# Radar_FMCW.net
KiCad netlist of a schematic drawn in Altium Designer
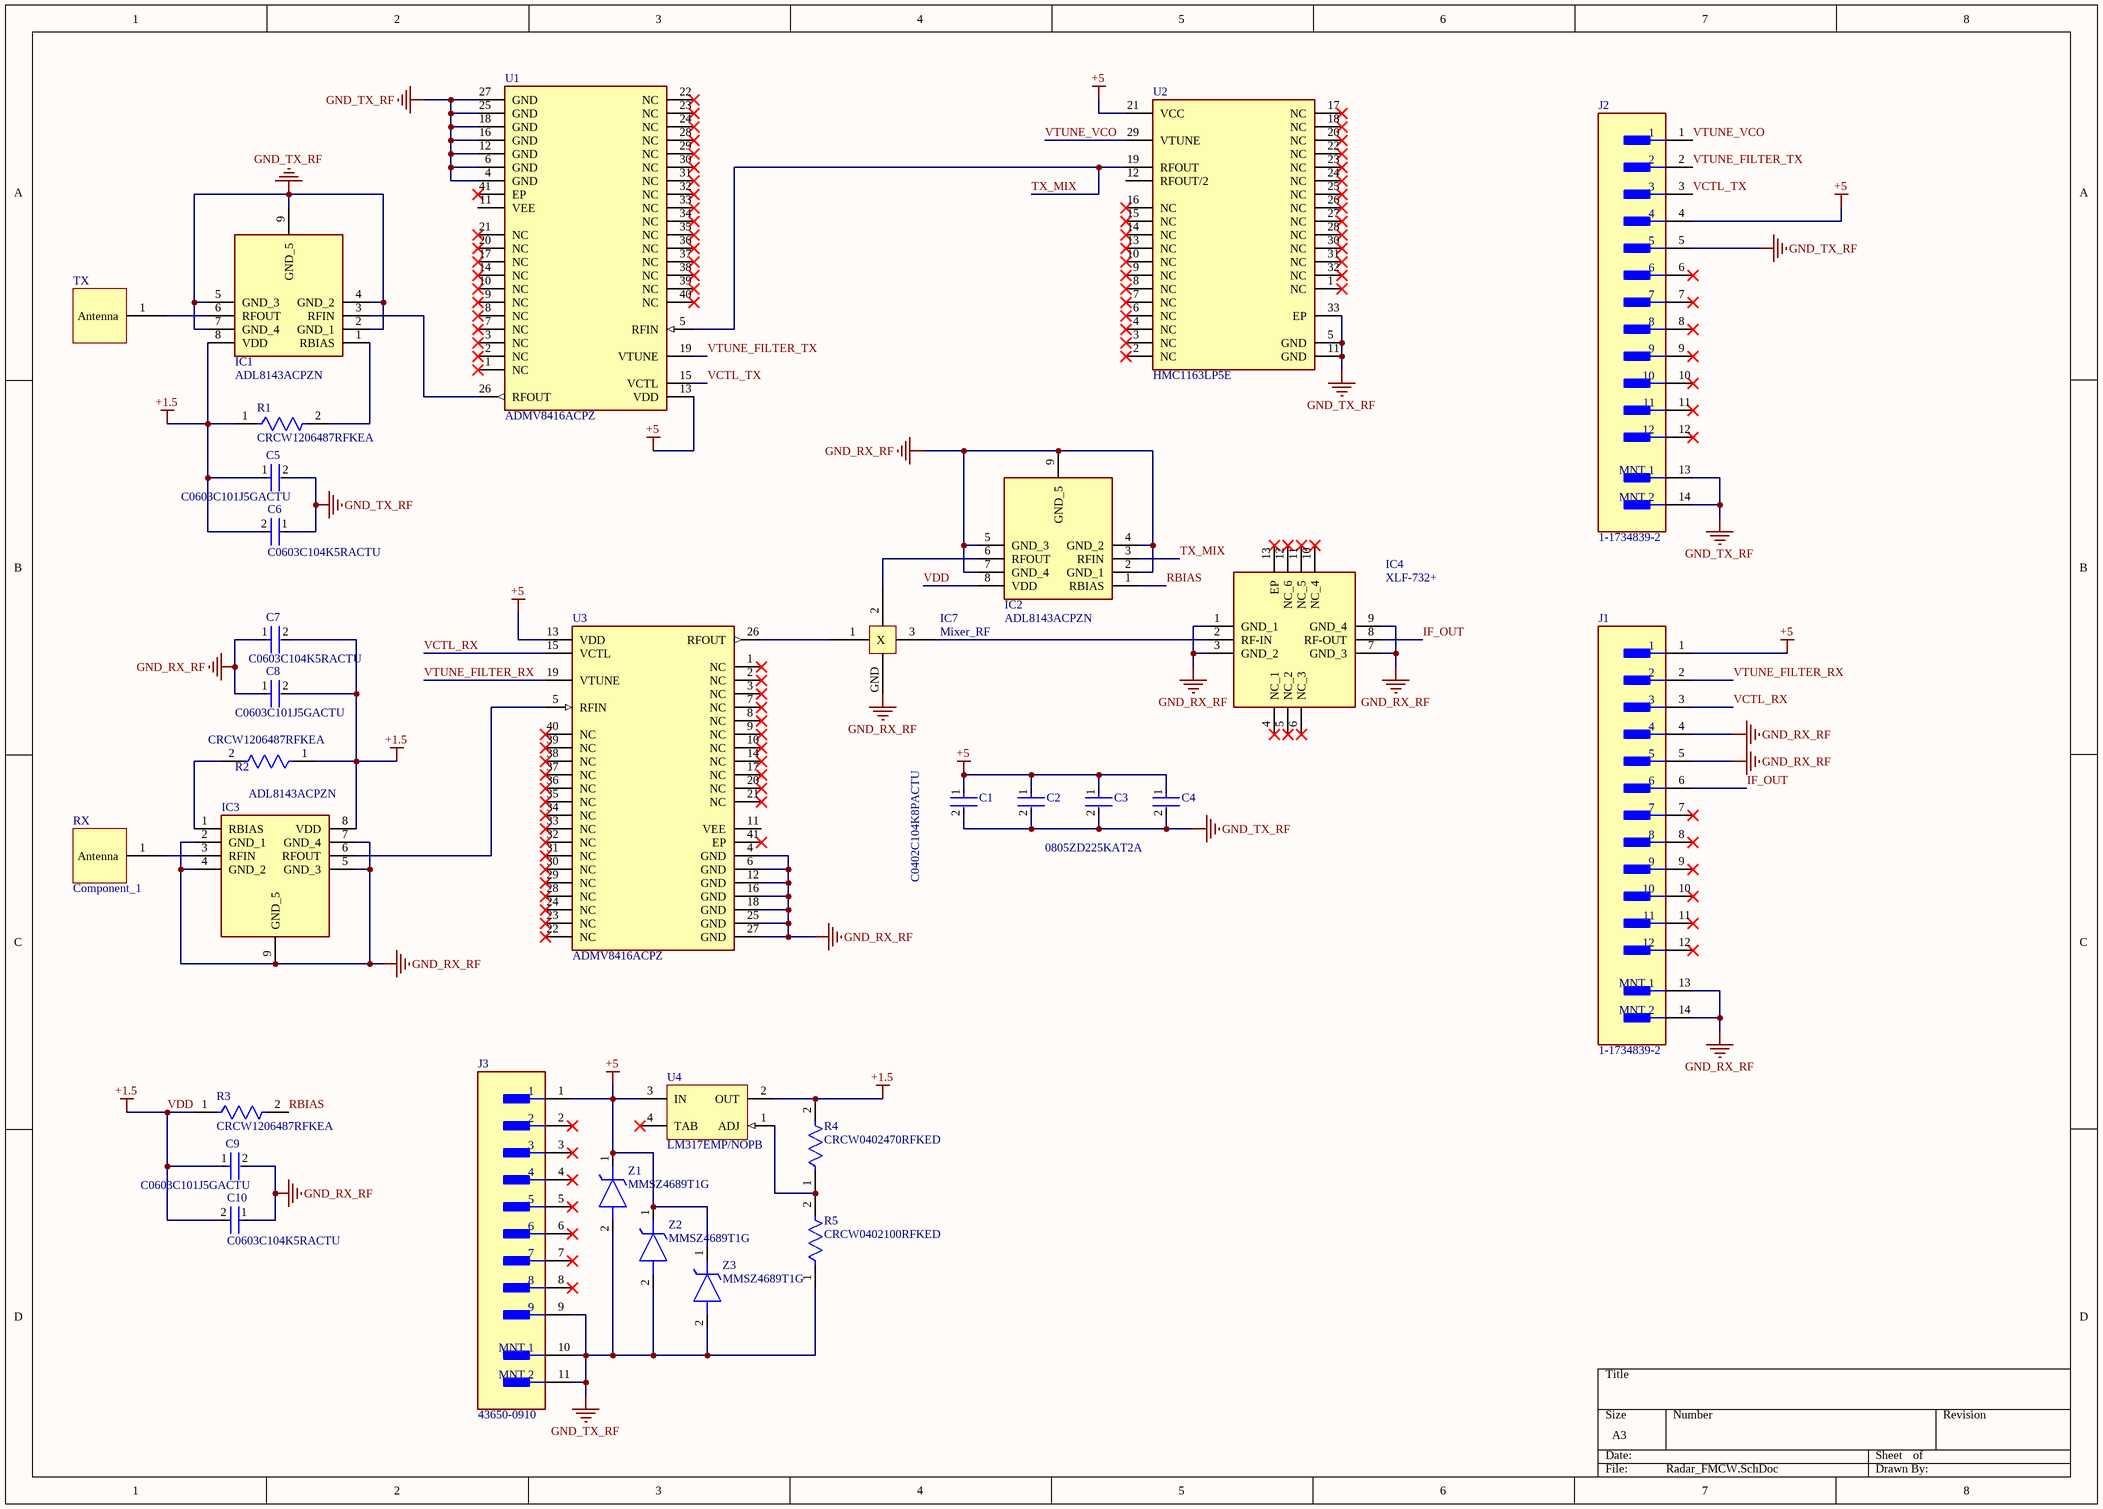
[diagram p0: Radar_FMCW.SchDoc]

(export (version "E")
  (design (tool "Eeschema 10.0.6"))
  (components
    (comp (ref "C1")
      (value "C0402C104K8PACTU")
      (footprint "FP-C0402-BB-MFG")
      (description "CAP CER 0.1UF 10V X5R 0402")
      (fields (field (name "MANUFACTURER") "Kemet") (field (name "TOLERANCE") "0.1"))
      (libsource (lib "Altium Content Vault") (part "b4654b650e69147ec39a6b967a45e02"))
    )
    (comp (ref "C2")
      (value "~")
      (footprint "FP-0805-L_2_01_0_2-W_1_25-IPC_B")
      (description "General Purpose Ceramic Capacitor, 0805, 2.2uF, 10%, X5R, 15%, 10V")
      (fields (field (name "VOLTAGE") "10V") (field (name "TOLERANCE") "10%"))
      (libsource (lib "Altium Content Vault") (part "b4654b650e69147ec39a6b967a45e02"))
    )
    (comp (ref "C3")
      (value "~")
      (footprint "FP-0805-L_2_01_0_2-W_1_25-IPC_B")
      (description "General Purpose Ceramic Capacitor, 0805, 2.2uF, 10%, X5R, 15%, 10V")
      (fields (field (name "VOLTAGE") "10V") (field (name "TOLERANCE") "10%"))
      (libsource (lib "Altium Content Vault") (part "b4654b650e69147ec39a6b967a45e02"))
    )
    (comp (ref "C4")
      (value "0805ZD225KAT2A")
      (footprint "FP-0805-L_2_01_0_2-W_1_25-IPC_B")
      (description "General Purpose Ceramic Capacitor, 0805, 2.2uF, 10%, X5R, 15%, 10V")
      (fields (field (name "VOLTAGE") "10V") (field (name "TOLERANCE") "10%"))
      (libsource (lib "Altium Content Vault") (part "b4654b650e69147ec39a6b967a45e02"))
    )
    (comp (ref "C5")
      (value "C0603C101J5GACTU")
      (footprint "FP-C0603C-CF-MFG")
      (description "CAP CER 100PF 50V C0G/NP0 0603")
      (fields (field (name "TOLERANCE") "0.05") (field (name "MANUFACTURER") "KEMET"))
      (libsource (lib "Altium Content Vault") (part "b4654b650e69147ec39a6b967a45e02"))
    )
    (comp (ref "C6")
      (value "C0603C104K5RACTU")
      (footprint "FP-C0603C-CF-MFG")
      (description "CAP CER 0.1UF 50V X7R 0603")
      (fields (field (name "TOLERANCE") "0.1") (field (name "MANUFACTURER") "KEMET"))
      (libsource (lib "Altium Content Vault") (part "b4654b650e69147ec39a6b967a45e02"))
    )
    (comp (ref "C7")
      (value "C0603C104K5RACTU")
      (footprint "FP-C0603C-CF-MFG")
      (description "CAP CER 0.1UF 50V X7R 0603")
      (fields (field (name "TOLERANCE") "0.1") (field (name "MANUFACTURER") "KEMET"))
      (libsource (lib "Altium Content Vault") (part "b4654b650e69147ec39a6b967a45e02"))
    )
    (comp (ref "C8")
      (value "C0603C101J5GACTU")
      (footprint "FP-C0603C-CF-MFG")
      (description "CAP CER 100PF 50V C0G/NP0 0603")
      (fields (field (name "TOLERANCE") "0.05") (field (name "MANUFACTURER") "KEMET"))
      (libsource (lib "Altium Content Vault") (part "b4654b650e69147ec39a6b967a45e02"))
    )
    (comp (ref "C9")
      (value "C0603C101J5GACTU")
      (footprint "FP-C0603C-CF-MFG")
      (description "CAP CER 100PF 50V C0G/NP0 0603")
      (fields (field (name "TOLERANCE") "0.05") (field (name "MANUFACTURER") "KEMET"))
      (libsource (lib "Altium Content Vault") (part "b4654b650e69147ec39a6b967a45e02"))
    )
    (comp (ref "C10")
      (value "C0603C104K5RACTU")
      (footprint "FP-C0603C-CF-MFG")
      (description "CAP CER 0.1UF 50V X7R 0603")
      (fields (field (name "TOLERANCE") "0.1") (field (name "MANUFACTURER") "KEMET"))
      (libsource (lib "Altium Content Vault") (part "b4654b650e69147ec39a6b967a45e02"))
    )
    (comp (ref "IC1")
      (value "ADL8143ACPZN")
      (footprint "SON50P200X200X90-9N-D")
      (description "Integrated Circuit")
      (libsource (lib "*") (part "ADL8143ACPZN"))
    )
    (comp (ref "IC2")
      (value "ADL8143ACPZN")
      (footprint "SON50P200X200X90-9N-D")
      (description "Integrated Circuit")
      (libsource (lib "*") (part "ADL8143ACPZN"))
    )
    (comp (ref "IC3")
      (value "ADL8143ACPZN")
      (footprint "SON50P200X200X90-9N-D")
      (description "Integrated Circuit")
      (libsource (lib "") (part "ADL8143ACPZN_1"))
    )
    (comp (ref "IC4")
      (value "XLF-732+")
      (footprint "QFN51P300X300X89-13N")
      (description "Integrated Circuit")
      (fields (field (name "MOUSER PART NUMBER") "139-XLF-732"))
      (libsource (lib "*") (part "XLF-732+"))
    )
    (comp (ref "IC7")
      (value "Mixer_RF")
      (footprint "Mixer_RF")
      (libsource (lib "Radar_FMCW") (part "Mixer_RF"))
    )
    (comp (ref "J1")
      (value "1-1734839-2")
      (footprint "FP-1-1734839-2-MFG")
      (description "CONN FPC TOP 12POS 0.50MM R/A")
      (libsource (lib "Altium Content Vault") (part "561d9104b8f291ee0c4fa0e805f8bc4"))
    )
    (comp (ref "J2")
      (value "1-1734839-2")
      (footprint "FP-1-1734839-2-MFG")
      (description "CONN FPC TOP 12POS 0.50MM R/A")
      (libsource (lib "Altium Content Vault") (part "561d9104b8f291ee0c4fa0e805f8bc4"))
    )
    (comp (ref "J3")
      (value "43650-0910")
      (footprint "FP-43650-0910-MFG")
      (description "43650-0910 Conn Power HDR 9 POS 3mm Solder RA SMD 9 Terminal 1 Port Micro-Fit 3.0™ Embossed T/R")
      (libsource (lib "Altium Content Vault") (part "1768e92021096bf704ffca471e34b85"))
    )
    (comp (ref "R1")
      (value "CRCW1206487RFKEA")
      (footprint "FP-CRCW1206-e3-MFG")
      (description "RES Thick Film, 487Ω, 1%, 0.25W, 100ppm/°C, 1206")
      (fields (field (name "TOLERANCE") "1%"))
      (libsource (lib "Altium Content Vault") (part "1029c3af85768c4190bb7ad29bc67b5"))
    )
    (comp (ref "R2")
      (value "CRCW1206487RFKEA")
      (footprint "FP-CRCW1206-e3-MFG")
      (description "RES Thick Film, 487Ω, 1%, 0.25W, 100ppm/°C, 1206")
      (fields (field (name "TOLERANCE") "1%"))
      (libsource (lib "Altium Content Vault") (part "1029c3af85768c4190bb7ad29bc67b5"))
    )
    (comp (ref "R3")
      (value "CRCW1206487RFKEA")
      (footprint "FP-CRCW1206-e3-MFG")
      (description "RES Thick Film, 487Ω, 1%, 0.25W, 100ppm/°C, 1206")
      (fields (field (name "TOLERANCE") "1%"))
      (libsource (lib "Altium Content Vault") (part "1029c3af85768c4190bb7ad29bc67b5"))
    )
    (comp (ref "R4")
      (value "CRCW0402470RFKED")
      (footprint "FP-CRCW0402-e3-MFG")
      (description "RES Thick Film, 470Ω, 1%, 0.063W, 100ppm/°C, 0402")
      (fields (field (name "TOLERANCE") "1%"))
      (libsource (lib "Altium Content Vault") (part "1029c3af85768c4190bb7ad29bc67b5"))
    )
    (comp (ref "R5")
      (value "CRCW0402100RFKED")
      (footprint "FP-CRCW0402-e3-IPC_C")
      (description "RES Thick Film, 100Ω, 1%, 0.063W, 100ppm/°C, 0402")
      (fields (field (name "TOLERANCE") "1%"))
      (libsource (lib "Altium Content Vault") (part "1029c3af85768c4190bb7ad29bc67b5"))
    )
    (comp (ref "RX")
      (value "Component_1")
      (footprint "Antenna_10GHz")
      (libsource (lib "Radar_FMCW") (part "Component_1"))
    )
    (comp (ref "TX")
      (value "~")
      (footprint "Antenna_10GHz")
      (libsource (lib "Radar_FMCW") (part "Component_1"))
    )
    (comp (ref "U1")
      (value "ADMV8416ACPZ")
      (footprint "FP-CP-40-27-IPC_C")
      (description "8 TO 16 GHZ TUNABLE BPF")
      (libsource (lib "Altium Content Vault") (part "eb4e6505d990d040ba8ad15b459702c"))
    )
    (comp (ref "U2")
      (value "HMC1163LP5E")
      (footprint "FP-HCP-32-1-IPC_B")
      (description "IC VCO VSAT 9.65-10.41GHZ 32CSP")
      (libsource (lib "Altium Content Vault") (part "3a6c81b600e4c804ad769945137bfc4"))
    )
    (comp (ref "U3")
      (value "ADMV8416ACPZ")
      (footprint "FP-CP-40-27-IPC_C")
      (description "8 TO 16 GHZ TUNABLE BPF")
      (libsource (lib "") (part "eb4e6505d990d040ba8ad15b459702c_1"))
    )
    (comp (ref "U4")
      (value "LM317EMP/NOPB")
      (footprint "DCY0004A_L")
      (description "3-Terminal Adjustable Regulator, 4-pin SOT-223, Pb-Free")
      (fields (field (name "MANUFACTURER") "Texas Instruments"))
      (libsource (lib "Altium Content Vault") (part "PM-REG-LM317ADJ-SOT4"))
    )
    (comp (ref "Z1")
      (value "MMSZ4689T1G")
      (footprint "Radar_FMCW:SOD3716X135N")
      (description "Zener Diode")
      (fields (field (name "MOUSER PART NUMBER") "863-MMSZ4689T1G"))
      (libsource (lib "*") (part "MMSZ4689T1G"))
    )
    (comp (ref "Z2")
      (value "MMSZ4689T1G")
      (footprint "Radar_FMCW:SOD3716X135N")
      (description "Zener Diode")
      (fields (field (name "MOUSER PART NUMBER") "863-MMSZ4689T1G"))
      (libsource (lib "*") (part "MMSZ4689T1G"))
    )
    (comp (ref "Z3")
      (value "MMSZ4689T1G")
      (footprint "Radar_FMCW:SOD3716X135N")
      (description "Zener Diode")
      (fields (field (name "MOUSER PART NUMBER") "863-MMSZ4689T1G"))
      (libsource (lib "*") (part "MMSZ4689T1G"))
    )
  )
  (nets
    (net (code "1") (name "+1.5") (class "Default")
      (node (ref "C10") (pin "2") (pinfunction "2_2") (pintype "passive"))
      (node (ref "C5") (pin "1") (pinfunction "1_1") (pintype "passive"))
      (node (ref "C6") (pin "2") (pinfunction "2_2") (pintype "passive"))
      (node (ref "C7") (pin "2") (pinfunction "2_2") (pintype "passive"))
      (node (ref "C8") (pin "2") (pinfunction "2_2") (pintype "passive"))
      (node (ref "C9") (pin "1") (pinfunction "1_1") (pintype "passive"))
      (node (ref "IC1") (pin "8") (pinfunction "VDD_8") (pintype "passive"))
      (node (ref "IC2") (pin "8") (pinfunction "VDD_8") (pintype "passive"))
      (node (ref "IC3") (pin "8") (pinfunction "VDD_8") (pintype "passive"))
      (node (ref "R1") (pin "1") (pinfunction "1_1") (pintype "passive"))
      (node (ref "R2") (pin "1") (pinfunction "1_1") (pintype "passive"))
      (node (ref "R3") (pin "1") (pinfunction "1_1") (pintype "passive"))
      (node (ref "R4") (pin "2") (pinfunction "2_2") (pintype "passive"))
      (node (ref "U4") (pin "2") (pinfunction "OUT_2") (pintype "power_in"))
    )
    (net (code "2") (name "+5") (class "Default")
      (node (ref "C1") (pin "1") (pinfunction "1_1") (pintype "passive"))
      (node (ref "C2") (pin "1") (pinfunction "1_1") (pintype "passive"))
      (node (ref "C3") (pin "1") (pinfunction "1_1") (pintype "passive"))
      (node (ref "C4") (pin "1") (pinfunction "1_1") (pintype "passive"))
      (node (ref "J1") (pin "1") (pinfunction "1_1") (pintype "passive"))
      (node (ref "J2") (pin "4") (pinfunction "4_4") (pintype "passive"))
      (node (ref "J3") (pin "1") (pinfunction "1_1") (pintype "passive"))
      (node (ref "U1") (pin "13") (pinfunction "VDD_13") (pintype "power_in"))
      (node (ref "U2") (pin "21") (pinfunction "VCC_21") (pintype "power_in"))
      (node (ref "U3") (pin "13") (pinfunction "VDD_13") (pintype "power_in"))
      (node (ref "U4") (pin "3") (pinfunction "IN_3") (pintype "power_in"))
      (node (ref "Z1") (pin "1") (pinfunction "K_1") (pintype "passive"))
      (node (ref "Z2") (pin "1") (pinfunction "K_1") (pintype "passive"))
      (node (ref "Z3") (pin "1") (pinfunction "K_1") (pintype "passive"))
    )
    (net (code "3") (name "/IF_OUT") (class "Default")
      (node (ref "IC4") (pin "8") (pinfunction "RF-OUT_8") (pintype "passive"))
      (node (ref "J1") (pin "6") (pinfunction "6_6") (pintype "passive"))
    )
    (net (code "4") (name "/RBIAS") (class "Default")
      (node (ref "IC2") (pin "1") (pinfunction "RBIAS_1") (pintype "passive"))
      (node (ref "R3") (pin "2") (pinfunction "2_2") (pintype "passive"))
    )
    (net (code "5") (name "/TX_MIX") (class "Default")
      (node (ref "IC2") (pin "3") (pinfunction "RFIN_3") (pintype "passive"))
      (node (ref "U1") (pin "5") (pinfunction "RFIN_5") (pintype "input"))
      (node (ref "U2") (pin "19") (pinfunction "RFOUT_19") (pintype "passive"))
    )
    (net (code "6") (name "/VCTL_RX") (class "Default")
      (node (ref "J1") (pin "3") (pinfunction "3_3") (pintype "passive"))
      (node (ref "U3") (pin "15") (pinfunction "VCTL_15") (pintype "power_in"))
    )
    (net (code "7") (name "/VCTL_TX") (class "Default")
      (node (ref "J2") (pin "3") (pinfunction "3_3") (pintype "passive"))
      (node (ref "U1") (pin "15") (pinfunction "VCTL_15") (pintype "power_in"))
    )
    (net (code "8") (name "/VTUNE_FILTER_RX") (class "Default")
      (node (ref "J1") (pin "2") (pinfunction "2_2") (pintype "passive"))
      (node (ref "U3") (pin "19") (pinfunction "VTUNE_19") (pintype "power_in"))
    )
    (net (code "9") (name "/VTUNE_FILTER_TX") (class "Default")
      (node (ref "J2") (pin "2") (pinfunction "2_2") (pintype "passive"))
      (node (ref "U1") (pin "19") (pinfunction "VTUNE_19") (pintype "power_in"))
    )
    (net (code "10") (name "/VTUNE_VCO") (class "Default")
      (node (ref "J2") (pin "1") (pinfunction "1_1") (pintype "passive"))
      (node (ref "U2") (pin "29") (pinfunction "VTUNE_29") (pintype "power_in"))
    )
    (net (code "11") (name "GND_RX_RF") (class "Default")
      (node (ref "C10") (pin "1") (pinfunction "1_1") (pintype "passive"))
      (node (ref "C7") (pin "1") (pinfunction "1_1") (pintype "passive"))
      (node (ref "C8") (pin "1") (pinfunction "1_1") (pintype "passive"))
      (node (ref "C9") (pin "2") (pinfunction "2_2") (pintype "passive"))
      (node (ref "IC2") (pin "2") (pinfunction "GND_1_2") (pintype "passive"))
      (node (ref "IC2") (pin "4") (pinfunction "GND_2_4") (pintype "passive"))
      (node (ref "IC2") (pin "5") (pinfunction "GND_3_5") (pintype "passive"))
      (node (ref "IC2") (pin "7") (pinfunction "GND_4_7") (pintype "passive"))
      (node (ref "IC2") (pin "9") (pinfunction "GND_5_9") (pintype "passive"))
      (node (ref "IC3") (pin "2") (pinfunction "GND_1_2") (pintype "passive"))
      (node (ref "IC3") (pin "4") (pinfunction "GND_2_4") (pintype "passive"))
      (node (ref "IC3") (pin "5") (pinfunction "GND_3_5") (pintype "passive"))
      (node (ref "IC3") (pin "7") (pinfunction "GND_4_7") (pintype "passive"))
      (node (ref "IC3") (pin "9") (pinfunction "GND_5_9") (pintype "passive"))
      (node (ref "IC4") (pin "1") (pinfunction "GND_1_1") (pintype "passive"))
      (node (ref "IC4") (pin "3") (pinfunction "GND_2_3") (pintype "passive"))
      (node (ref "IC4") (pin "7") (pinfunction "GND_3_7") (pintype "passive"))
      (node (ref "IC4") (pin "9") (pinfunction "GND_4_9") (pintype "passive"))
      (node (ref "IC7") (pin "GND") (pintype "passive"))
      (node (ref "J1") (pin "13") (pinfunction "MNT_1_13") (pintype "passive"))
      (node (ref "J1") (pin "14") (pinfunction "MNT_2_14") (pintype "passive"))
      (node (ref "J1") (pin "4") (pinfunction "4_4") (pintype "passive"))
      (node (ref "J1") (pin "5") (pinfunction "5_5") (pintype "passive"))
      (node (ref "U3") (pin "12") (pinfunction "GND_12") (pintype "power_in"))
      (node (ref "U3") (pin "16") (pinfunction "GND_16") (pintype "power_in"))
      (node (ref "U3") (pin "18") (pinfunction "GND_18") (pintype "power_in"))
      (node (ref "U3") (pin "25") (pinfunction "GND_25") (pintype "power_in"))
      (node (ref "U3") (pin "27") (pinfunction "GND_27") (pintype "power_in"))
      (node (ref "U3") (pin "4") (pinfunction "GND_4") (pintype "power_in"))
      (node (ref "U3") (pin "6") (pinfunction "GND_6") (pintype "power_in"))
    )
    (net (code "12") (name "GND_TX_RF") (class "Default")
      (node (ref "C1") (pin "2") (pinfunction "2_2") (pintype "passive"))
      (node (ref "C2") (pin "2") (pinfunction "2_2") (pintype "passive"))
      (node (ref "C3") (pin "2") (pinfunction "2_2") (pintype "passive"))
      (node (ref "C4") (pin "2") (pinfunction "2_2") (pintype "passive"))
      (node (ref "C5") (pin "2") (pinfunction "2_2") (pintype "passive"))
      (node (ref "C6") (pin "1") (pinfunction "1_1") (pintype "passive"))
      (node (ref "IC1") (pin "2") (pinfunction "GND_1_2") (pintype "passive"))
      (node (ref "IC1") (pin "4") (pinfunction "GND_2_4") (pintype "passive"))
      (node (ref "IC1") (pin "5") (pinfunction "GND_3_5") (pintype "passive"))
      (node (ref "IC1") (pin "7") (pinfunction "GND_4_7") (pintype "passive"))
      (node (ref "IC1") (pin "9") (pinfunction "GND_5_9") (pintype "passive"))
      (node (ref "J2") (pin "13") (pinfunction "MNT_1_13") (pintype "passive"))
      (node (ref "J2") (pin "14") (pinfunction "MNT_2_14") (pintype "passive"))
      (node (ref "J2") (pin "5") (pinfunction "5_5") (pintype "passive"))
      (node (ref "J3") (pin "10") (pinfunction "MNT_1_10") (pintype "passive"))
      (node (ref "J3") (pin "11") (pinfunction "MNT_2_11") (pintype "passive"))
      (node (ref "J3") (pin "9") (pinfunction "9_9") (pintype "passive"))
      (node (ref "R5") (pin "1") (pinfunction "1_1") (pintype "passive"))
      (node (ref "U1") (pin "12") (pinfunction "GND_12") (pintype "power_in"))
      (node (ref "U1") (pin "16") (pinfunction "GND_16") (pintype "power_in"))
      (node (ref "U1") (pin "18") (pinfunction "GND_18") (pintype "power_in"))
      (node (ref "U1") (pin "25") (pinfunction "GND_25") (pintype "power_in"))
      (node (ref "U1") (pin "27") (pinfunction "GND_27") (pintype "power_in"))
      (node (ref "U1") (pin "4") (pinfunction "GND_4") (pintype "power_in"))
      (node (ref "U1") (pin "6") (pinfunction "GND_6") (pintype "power_in"))
      (node (ref "U2") (pin "11") (pinfunction "GND_11") (pintype "power_in"))
      (node (ref "U2") (pin "33") (pinfunction "EP_33") (pintype "passive"))
      (node (ref "U2") (pin "5") (pinfunction "GND_5") (pintype "power_in"))
      (node (ref "Z1") (pin "2") (pinfunction "A_2") (pintype "passive"))
      (node (ref "Z2") (pin "2") (pinfunction "A_2") (pintype "passive"))
      (node (ref "Z3") (pin "2") (pinfunction "A_2") (pintype "passive"))
    )
    (net (code "13") (name "Net-(IC1-RBIAS)") (class "Default")
      (node (ref "IC1") (pin "1") (pinfunction "RBIAS_1") (pintype "passive"))
      (node (ref "R1") (pin "2") (pinfunction "2_2") (pintype "passive"))
    )
    (net (code "14") (name "Net-(IC1-RFIN)") (class "Default")
      (node (ref "IC1") (pin "3") (pinfunction "RFIN_3") (pintype "passive"))
      (node (ref "U1") (pin "26") (pinfunction "RFOUT_26") (pintype "output"))
    )
    (net (code "15") (name "Net-(IC1-RFOUT)") (class "Default")
      (node (ref "IC1") (pin "6") (pinfunction "RFOUT_6") (pintype "passive"))
      (node (ref "TX") (pin "1") (pinfunction "Antenna_1") (pintype "passive"))
    )
    (net (code "16") (name "Net-(IC2-RFOUT)") (class "Default")
      (node (ref "IC2") (pin "6") (pinfunction "RFOUT_6") (pintype "passive"))
      (node (ref "IC7") (pin "2") (pintype "passive"))
    )
    (net (code "17") (name "Net-(IC3-RBIAS)") (class "Default")
      (node (ref "IC3") (pin "1") (pinfunction "RBIAS_1") (pintype "passive"))
      (node (ref "R2") (pin "2") (pinfunction "2_2") (pintype "passive"))
    )
    (net (code "18") (name "Net-(IC3-RFIN)") (class "Default")
      (node (ref "IC3") (pin "3") (pinfunction "RFIN_3") (pintype "passive"))
      (node (ref "RX") (pin "1") (pinfunction "Antenna_1") (pintype "passive"))
    )
    (net (code "19") (name "Net-(IC3-RFOUT)") (class "Default")
      (node (ref "IC3") (pin "6") (pinfunction "RFOUT_6") (pintype "passive"))
      (node (ref "U3") (pin "5") (pinfunction "RFIN_5") (pintype "input"))
    )
    (net (code "20") (name "Net-(IC4-RF-IN)") (class "Default")
      (node (ref "IC4") (pin "2") (pinfunction "RF-IN_2") (pintype "passive"))
      (node (ref "IC7") (pin "3") (pintype "passive"))
    )
    (net (code "21") (name "Net-(IC7-X)") (class "Default")
      (node (ref "IC7") (pin "1") (pinfunction "X_1") (pintype "passive"))
      (node (ref "U3") (pin "26") (pinfunction "RFOUT_26") (pintype "output"))
    )
    (net (code "22") (name "Net-(U4-ADJ)") (class "Default")
      (node (ref "R4") (pin "1") (pinfunction "1_1") (pintype "passive"))
      (node (ref "R5") (pin "2") (pinfunction "2_2") (pintype "passive"))
      (node (ref "U4") (pin "1") (pinfunction "ADJ_1") (pintype "input"))
    )
    (net (code "23") (name "unconnected-(IC4-EP-Pad13)") (class "Default")
      (node (ref "IC4") (pin "13") (pinfunction "EP_13") (pintype "passive+no_connect"))
    )
    (net (code "24") (name "unconnected-(IC4-NC_1-Pad4)") (class "Default")
      (node (ref "IC4") (pin "4") (pinfunction "NC_1_4") (pintype "passive+no_connect"))
    )
    (net (code "25") (name "unconnected-(IC4-NC_2-Pad5)") (class "Default")
      (node (ref "IC4") (pin "5") (pinfunction "NC_2_5") (pintype "passive+no_connect"))
    )
    (net (code "26") (name "unconnected-(IC4-NC_3-Pad6)") (class "Default")
      (node (ref "IC4") (pin "6") (pinfunction "NC_3_6") (pintype "passive+no_connect"))
    )
    (net (code "27") (name "unconnected-(IC4-NC_4-Pad10)") (class "Default")
      (node (ref "IC4") (pin "10") (pinfunction "NC_4_10") (pintype "passive+no_connect"))
    )
    (net (code "28") (name "unconnected-(IC4-NC_5-Pad11)") (class "Default")
      (node (ref "IC4") (pin "11") (pinfunction "NC_5_11") (pintype "passive+no_connect"))
    )
    (net (code "29") (name "unconnected-(IC4-NC_6-Pad12)") (class "Default")
      (node (ref "IC4") (pin "12") (pinfunction "NC_6_12") (pintype "passive+no_connect"))
    )
    (net (code "30") (name "unconnected-(J1-Pad7)") (class "Default")
      (node (ref "J1") (pin "7") (pinfunction "7_7") (pintype "passive+no_connect"))
    )
    (net (code "31") (name "unconnected-(J1-Pad8)") (class "Default")
      (node (ref "J1") (pin "8") (pinfunction "8_8") (pintype "passive+no_connect"))
    )
    (net (code "32") (name "unconnected-(J1-Pad9)") (class "Default")
      (node (ref "J1") (pin "9") (pinfunction "9_9") (pintype "passive+no_connect"))
    )
    (net (code "33") (name "unconnected-(J1-Pad10)") (class "Default")
      (node (ref "J1") (pin "10") (pinfunction "10_10") (pintype "passive+no_connect"))
    )
    (net (code "34") (name "unconnected-(J1-Pad11)") (class "Default")
      (node (ref "J1") (pin "11") (pinfunction "11_11") (pintype "passive+no_connect"))
    )
    (net (code "35") (name "unconnected-(J1-Pad12)") (class "Default")
      (node (ref "J1") (pin "12") (pinfunction "12_12") (pintype "passive+no_connect"))
    )
    (net (code "36") (name "unconnected-(J2-Pad6)") (class "Default")
      (node (ref "J2") (pin "6") (pinfunction "6_6") (pintype "passive+no_connect"))
    )
    (net (code "37") (name "unconnected-(J2-Pad7)") (class "Default")
      (node (ref "J2") (pin "7") (pinfunction "7_7") (pintype "passive+no_connect"))
    )
    (net (code "38") (name "unconnected-(J2-Pad8)") (class "Default")
      (node (ref "J2") (pin "8") (pinfunction "8_8") (pintype "passive+no_connect"))
    )
    (net (code "39") (name "unconnected-(J2-Pad9)") (class "Default")
      (node (ref "J2") (pin "9") (pinfunction "9_9") (pintype "passive+no_connect"))
    )
    (net (code "40") (name "unconnected-(J2-Pad10)") (class "Default")
      (node (ref "J2") (pin "10") (pinfunction "10_10") (pintype "passive+no_connect"))
    )
    (net (code "41") (name "unconnected-(J2-Pad11)") (class "Default")
      (node (ref "J2") (pin "11") (pinfunction "11_11") (pintype "passive+no_connect"))
    )
    (net (code "42") (name "unconnected-(J2-Pad12)") (class "Default")
      (node (ref "J2") (pin "12") (pinfunction "12_12") (pintype "passive+no_connect"))
    )
    (net (code "43") (name "unconnected-(J3-Pad2)") (class "Default")
      (node (ref "J3") (pin "2") (pinfunction "2_2") (pintype "passive+no_connect"))
    )
    (net (code "44") (name "unconnected-(J3-Pad3)") (class "Default")
      (node (ref "J3") (pin "3") (pinfunction "3_3") (pintype "passive+no_connect"))
    )
    (net (code "45") (name "unconnected-(J3-Pad4)") (class "Default")
      (node (ref "J3") (pin "4") (pinfunction "4_4") (pintype "passive+no_connect"))
    )
    (net (code "46") (name "unconnected-(J3-Pad5)") (class "Default")
      (node (ref "J3") (pin "5") (pinfunction "5_5") (pintype "passive+no_connect"))
    )
    (net (code "47") (name "unconnected-(J3-Pad6)") (class "Default")
      (node (ref "J3") (pin "6") (pinfunction "6_6") (pintype "passive+no_connect"))
    )
    (net (code "48") (name "unconnected-(J3-Pad7)") (class "Default")
      (node (ref "J3") (pin "7") (pinfunction "7_7") (pintype "passive+no_connect"))
    )
    (net (code "49") (name "unconnected-(J3-Pad8)") (class "Default")
      (node (ref "J3") (pin "8") (pinfunction "8_8") (pintype "passive+no_connect"))
    )
    (net (code "50") (name "unconnected-(U1-EP-Pad41)") (class "Default")
      (node (ref "U1") (pin "41") (pinfunction "EP_41") (pintype "passive+no_connect"))
    )
    (net (code "51") (name "unconnected-(U1-NC-Pad1)") (class "Default")
      (node (ref "U1") (pin "1") (pinfunction "NC_1") (pintype "passive+no_connect"))
    )
    (net (code "52") (name "unconnected-(U1-NC-Pad2)") (class "Default")
      (node (ref "U1") (pin "2") (pinfunction "NC_2") (pintype "passive+no_connect"))
    )
    (net (code "53") (name "unconnected-(U1-NC-Pad3)") (class "Default")
      (node (ref "U1") (pin "3") (pinfunction "NC_3") (pintype "passive+no_connect"))
    )
    (net (code "54") (name "unconnected-(U1-NC-Pad7)") (class "Default")
      (node (ref "U1") (pin "7") (pinfunction "NC_7") (pintype "passive+no_connect"))
    )
    (net (code "55") (name "unconnected-(U1-NC-Pad8)") (class "Default")
      (node (ref "U1") (pin "8") (pinfunction "NC_8") (pintype "passive+no_connect"))
    )
    (net (code "56") (name "unconnected-(U1-NC-Pad9)") (class "Default")
      (node (ref "U1") (pin "9") (pinfunction "NC_9") (pintype "passive+no_connect"))
    )
    (net (code "57") (name "unconnected-(U1-NC-Pad10)") (class "Default")
      (node (ref "U1") (pin "10") (pinfunction "NC_10") (pintype "passive+no_connect"))
    )
    (net (code "58") (name "unconnected-(U1-NC-Pad14)") (class "Default")
      (node (ref "U1") (pin "14") (pinfunction "NC_14") (pintype "passive+no_connect"))
    )
    (net (code "59") (name "unconnected-(U1-NC-Pad17)") (class "Default")
      (node (ref "U1") (pin "17") (pinfunction "NC_17") (pintype "passive+no_connect"))
    )
    (net (code "60") (name "unconnected-(U1-NC-Pad20)") (class "Default")
      (node (ref "U1") (pin "20") (pinfunction "NC_20") (pintype "passive+no_connect"))
    )
    (net (code "61") (name "unconnected-(U1-NC-Pad21)") (class "Default")
      (node (ref "U1") (pin "21") (pinfunction "NC_21") (pintype "passive+no_connect"))
    )
    (net (code "62") (name "unconnected-(U1-NC-Pad22)") (class "Default")
      (node (ref "U1") (pin "22") (pinfunction "NC_22") (pintype "passive+no_connect"))
    )
    (net (code "63") (name "unconnected-(U1-NC-Pad23)") (class "Default")
      (node (ref "U1") (pin "23") (pinfunction "NC_23") (pintype "passive+no_connect"))
    )
    (net (code "64") (name "unconnected-(U1-NC-Pad24)") (class "Default")
      (node (ref "U1") (pin "24") (pinfunction "NC_24") (pintype "passive+no_connect"))
    )
    (net (code "65") (name "unconnected-(U1-NC-Pad28)") (class "Default")
      (node (ref "U1") (pin "28") (pinfunction "NC_28") (pintype "passive+no_connect"))
    )
    (net (code "66") (name "unconnected-(U1-NC-Pad29)") (class "Default")
      (node (ref "U1") (pin "29") (pinfunction "NC_29") (pintype "passive+no_connect"))
    )
    (net (code "67") (name "unconnected-(U1-NC-Pad30)") (class "Default")
      (node (ref "U1") (pin "30") (pinfunction "NC_30") (pintype "passive+no_connect"))
    )
    (net (code "68") (name "unconnected-(U1-NC-Pad31)") (class "Default")
      (node (ref "U1") (pin "31") (pinfunction "NC_31") (pintype "passive+no_connect"))
    )
    (net (code "69") (name "unconnected-(U1-NC-Pad32)") (class "Default")
      (node (ref "U1") (pin "32") (pinfunction "NC_32") (pintype "passive+no_connect"))
    )
    (net (code "70") (name "unconnected-(U1-NC-Pad33)") (class "Default")
      (node (ref "U1") (pin "33") (pinfunction "NC_33") (pintype "passive+no_connect"))
    )
    (net (code "71") (name "unconnected-(U1-NC-Pad34)") (class "Default")
      (node (ref "U1") (pin "34") (pinfunction "NC_34") (pintype "passive+no_connect"))
    )
    (net (code "72") (name "unconnected-(U1-NC-Pad35)") (class "Default")
      (node (ref "U1") (pin "35") (pinfunction "NC_35") (pintype "passive+no_connect"))
    )
    (net (code "73") (name "unconnected-(U1-NC-Pad36)") (class "Default")
      (node (ref "U1") (pin "36") (pinfunction "NC_36") (pintype "passive+no_connect"))
    )
    (net (code "74") (name "unconnected-(U1-NC-Pad37)") (class "Default")
      (node (ref "U1") (pin "37") (pinfunction "NC_37") (pintype "passive+no_connect"))
    )
    (net (code "75") (name "unconnected-(U1-NC-Pad38)") (class "Default")
      (node (ref "U1") (pin "38") (pinfunction "NC_38") (pintype "passive+no_connect"))
    )
    (net (code "76") (name "unconnected-(U1-NC-Pad39)") (class "Default")
      (node (ref "U1") (pin "39") (pinfunction "NC_39") (pintype "passive+no_connect"))
    )
    (net (code "77") (name "unconnected-(U1-NC-Pad40)") (class "Default")
      (node (ref "U1") (pin "40") (pinfunction "NC_40") (pintype "passive+no_connect"))
    )
    (net (code "78") (name "unconnected-(U1-VEE-Pad11)") (class "Default")
      (node (ref "U1") (pin "11") (pinfunction "VEE_11") (pintype "power_in"))
    )
    (net (code "79") (name "unconnected-(U2-NC-Pad1)") (class "Default")
      (node (ref "U2") (pin "1") (pinfunction "NC_1") (pintype "passive+no_connect"))
    )
    (net (code "80") (name "unconnected-(U2-NC-Pad2)") (class "Default")
      (node (ref "U2") (pin "2") (pinfunction "NC_2") (pintype "passive+no_connect"))
    )
    (net (code "81") (name "unconnected-(U2-NC-Pad3)") (class "Default")
      (node (ref "U2") (pin "3") (pinfunction "NC_3") (pintype "passive+no_connect"))
    )
    (net (code "82") (name "unconnected-(U2-NC-Pad4)") (class "Default")
      (node (ref "U2") (pin "4") (pinfunction "NC_4") (pintype "passive+no_connect"))
    )
    (net (code "83") (name "unconnected-(U2-NC-Pad6)") (class "Default")
      (node (ref "U2") (pin "6") (pinfunction "NC_6") (pintype "passive+no_connect"))
    )
    (net (code "84") (name "unconnected-(U2-NC-Pad7)") (class "Default")
      (node (ref "U2") (pin "7") (pinfunction "NC_7") (pintype "passive+no_connect"))
    )
    (net (code "85") (name "unconnected-(U2-NC-Pad8)") (class "Default")
      (node (ref "U2") (pin "8") (pinfunction "NC_8") (pintype "passive+no_connect"))
    )
    (net (code "86") (name "unconnected-(U2-NC-Pad9)") (class "Default")
      (node (ref "U2") (pin "9") (pinfunction "NC_9") (pintype "passive+no_connect"))
    )
    (net (code "87") (name "unconnected-(U2-NC-Pad10)") (class "Default")
      (node (ref "U2") (pin "10") (pinfunction "NC_10") (pintype "passive+no_connect"))
    )
    (net (code "88") (name "unconnected-(U2-NC-Pad13)") (class "Default")
      (node (ref "U2") (pin "13") (pinfunction "NC_13") (pintype "passive+no_connect"))
    )
    (net (code "89") (name "unconnected-(U2-NC-Pad14)") (class "Default")
      (node (ref "U2") (pin "14") (pinfunction "NC_14") (pintype "passive+no_connect"))
    )
    (net (code "90") (name "unconnected-(U2-NC-Pad15)") (class "Default")
      (node (ref "U2") (pin "15") (pinfunction "NC_15") (pintype "passive+no_connect"))
    )
    (net (code "91") (name "unconnected-(U2-NC-Pad16)") (class "Default")
      (node (ref "U2") (pin "16") (pinfunction "NC_16") (pintype "passive+no_connect"))
    )
    (net (code "92") (name "unconnected-(U2-NC-Pad17)") (class "Default")
      (node (ref "U2") (pin "17") (pinfunction "NC_17") (pintype "passive+no_connect"))
    )
    (net (code "93") (name "unconnected-(U2-NC-Pad18)") (class "Default")
      (node (ref "U2") (pin "18") (pinfunction "NC_18") (pintype "passive+no_connect"))
    )
    (net (code "94") (name "unconnected-(U2-NC-Pad20)") (class "Default")
      (node (ref "U2") (pin "20") (pinfunction "NC_20") (pintype "passive+no_connect"))
    )
    (net (code "95") (name "unconnected-(U2-NC-Pad22)") (class "Default")
      (node (ref "U2") (pin "22") (pinfunction "NC_22") (pintype "passive+no_connect"))
    )
    (net (code "96") (name "unconnected-(U2-NC-Pad23)") (class "Default")
      (node (ref "U2") (pin "23") (pinfunction "NC_23") (pintype "passive+no_connect"))
    )
    (net (code "97") (name "unconnected-(U2-NC-Pad24)") (class "Default")
      (node (ref "U2") (pin "24") (pinfunction "NC_24") (pintype "passive+no_connect"))
    )
    (net (code "98") (name "unconnected-(U2-NC-Pad25)") (class "Default")
      (node (ref "U2") (pin "25") (pinfunction "NC_25") (pintype "passive+no_connect"))
    )
    (net (code "99") (name "unconnected-(U2-NC-Pad26)") (class "Default")
      (node (ref "U2") (pin "26") (pinfunction "NC_26") (pintype "passive+no_connect"))
    )
    (net (code "100") (name "unconnected-(U2-NC-Pad27)") (class "Default")
      (node (ref "U2") (pin "27") (pinfunction "NC_27") (pintype "passive+no_connect"))
    )
    (net (code "101") (name "unconnected-(U2-NC-Pad28)") (class "Default")
      (node (ref "U2") (pin "28") (pinfunction "NC_28") (pintype "passive+no_connect"))
    )
    (net (code "102") (name "unconnected-(U2-NC-Pad30)") (class "Default")
      (node (ref "U2") (pin "30") (pinfunction "NC_30") (pintype "passive+no_connect"))
    )
    (net (code "103") (name "unconnected-(U2-NC-Pad31)") (class "Default")
      (node (ref "U2") (pin "31") (pinfunction "NC_31") (pintype "passive+no_connect"))
    )
    (net (code "104") (name "unconnected-(U2-NC-Pad32)") (class "Default")
      (node (ref "U2") (pin "32") (pinfunction "NC_32") (pintype "passive+no_connect"))
    )
    (net (code "105") (name "unconnected-(U2-RFOUT{slash}2-Pad12)") (class "Default")
      (node (ref "U2") (pin "12") (pinfunction "RFOUT/2_12") (pintype "passive"))
    )
    (net (code "106") (name "unconnected-(U3-EP-Pad41)") (class "Default")
      (node (ref "U3") (pin "41") (pinfunction "EP_41") (pintype "passive+no_connect"))
    )
    (net (code "107") (name "unconnected-(U3-NC-Pad1)") (class "Default")
      (node (ref "U3") (pin "1") (pinfunction "NC_1") (pintype "passive+no_connect"))
    )
    (net (code "108") (name "unconnected-(U3-NC-Pad2)") (class "Default")
      (node (ref "U3") (pin "2") (pinfunction "NC_2") (pintype "passive+no_connect"))
    )
    (net (code "109") (name "unconnected-(U3-NC-Pad3)") (class "Default")
      (node (ref "U3") (pin "3") (pinfunction "NC_3") (pintype "passive+no_connect"))
    )
    (net (code "110") (name "unconnected-(U3-NC-Pad7)") (class "Default")
      (node (ref "U3") (pin "7") (pinfunction "NC_7") (pintype "passive+no_connect"))
    )
    (net (code "111") (name "unconnected-(U3-NC-Pad8)") (class "Default")
      (node (ref "U3") (pin "8") (pinfunction "NC_8") (pintype "passive+no_connect"))
    )
    (net (code "112") (name "unconnected-(U3-NC-Pad9)") (class "Default")
      (node (ref "U3") (pin "9") (pinfunction "NC_9") (pintype "passive+no_connect"))
    )
    (net (code "113") (name "unconnected-(U3-NC-Pad10)") (class "Default")
      (node (ref "U3") (pin "10") (pinfunction "NC_10") (pintype "passive+no_connect"))
    )
    (net (code "114") (name "unconnected-(U3-NC-Pad14)") (class "Default")
      (node (ref "U3") (pin "14") (pinfunction "NC_14") (pintype "passive+no_connect"))
    )
    (net (code "115") (name "unconnected-(U3-NC-Pad17)") (class "Default")
      (node (ref "U3") (pin "17") (pinfunction "NC_17") (pintype "passive+no_connect"))
    )
    (net (code "116") (name "unconnected-(U3-NC-Pad20)") (class "Default")
      (node (ref "U3") (pin "20") (pinfunction "NC_20") (pintype "passive+no_connect"))
    )
    (net (code "117") (name "unconnected-(U3-NC-Pad21)") (class "Default")
      (node (ref "U3") (pin "21") (pinfunction "NC_21") (pintype "passive+no_connect"))
    )
    (net (code "118") (name "unconnected-(U3-NC-Pad22)") (class "Default")
      (node (ref "U3") (pin "22") (pinfunction "NC_22") (pintype "passive+no_connect"))
    )
    (net (code "119") (name "unconnected-(U3-NC-Pad23)") (class "Default")
      (node (ref "U3") (pin "23") (pinfunction "NC_23") (pintype "passive+no_connect"))
    )
    (net (code "120") (name "unconnected-(U3-NC-Pad24)") (class "Default")
      (node (ref "U3") (pin "24") (pinfunction "NC_24") (pintype "passive+no_connect"))
    )
    (net (code "121") (name "unconnected-(U3-NC-Pad28)") (class "Default")
      (node (ref "U3") (pin "28") (pinfunction "NC_28") (pintype "passive+no_connect"))
    )
    (net (code "122") (name "unconnected-(U3-NC-Pad29)") (class "Default")
      (node (ref "U3") (pin "29") (pinfunction "NC_29") (pintype "passive+no_connect"))
    )
    (net (code "123") (name "unconnected-(U3-NC-Pad30)") (class "Default")
      (node (ref "U3") (pin "30") (pinfunction "NC_30") (pintype "passive+no_connect"))
    )
    (net (code "124") (name "unconnected-(U3-NC-Pad31)") (class "Default")
      (node (ref "U3") (pin "31") (pinfunction "NC_31") (pintype "passive+no_connect"))
    )
    (net (code "125") (name "unconnected-(U3-NC-Pad32)") (class "Default")
      (node (ref "U3") (pin "32") (pinfunction "NC_32") (pintype "passive+no_connect"))
    )
    (net (code "126") (name "unconnected-(U3-NC-Pad33)") (class "Default")
      (node (ref "U3") (pin "33") (pinfunction "NC_33") (pintype "passive+no_connect"))
    )
    (net (code "127") (name "unconnected-(U3-NC-Pad34)") (class "Default")
      (node (ref "U3") (pin "34") (pinfunction "NC_34") (pintype "passive+no_connect"))
    )
    (net (code "128") (name "unconnected-(U3-NC-Pad35)") (class "Default")
      (node (ref "U3") (pin "35") (pinfunction "NC_35") (pintype "passive+no_connect"))
    )
    (net (code "129") (name "unconnected-(U3-NC-Pad36)") (class "Default")
      (node (ref "U3") (pin "36") (pinfunction "NC_36") (pintype "passive+no_connect"))
    )
    (net (code "130") (name "unconnected-(U3-NC-Pad37)") (class "Default")
      (node (ref "U3") (pin "37") (pinfunction "NC_37") (pintype "passive+no_connect"))
    )
    (net (code "131") (name "unconnected-(U3-NC-Pad38)") (class "Default")
      (node (ref "U3") (pin "38") (pinfunction "NC_38") (pintype "passive+no_connect"))
    )
    (net (code "132") (name "unconnected-(U3-NC-Pad39)") (class "Default")
      (node (ref "U3") (pin "39") (pinfunction "NC_39") (pintype "passive+no_connect"))
    )
    (net (code "133") (name "unconnected-(U3-NC-Pad40)") (class "Default")
      (node (ref "U3") (pin "40") (pinfunction "NC_40") (pintype "passive+no_connect"))
    )
    (net (code "134") (name "unconnected-(U3-VEE-Pad11)") (class "Default")
      (node (ref "U3") (pin "11") (pinfunction "VEE_11") (pintype "power_in"))
    )
    (net (code "135") (name "unconnected-(U4-TAB-Pad4)") (class "Default")
      (node (ref "U4") (pin "4") (pinfunction "TAB_4") (pintype "power_in+no_connect"))
    )
  )
)
